# trezor.net
KiCad netlist of a schematic drawn in EAGLE
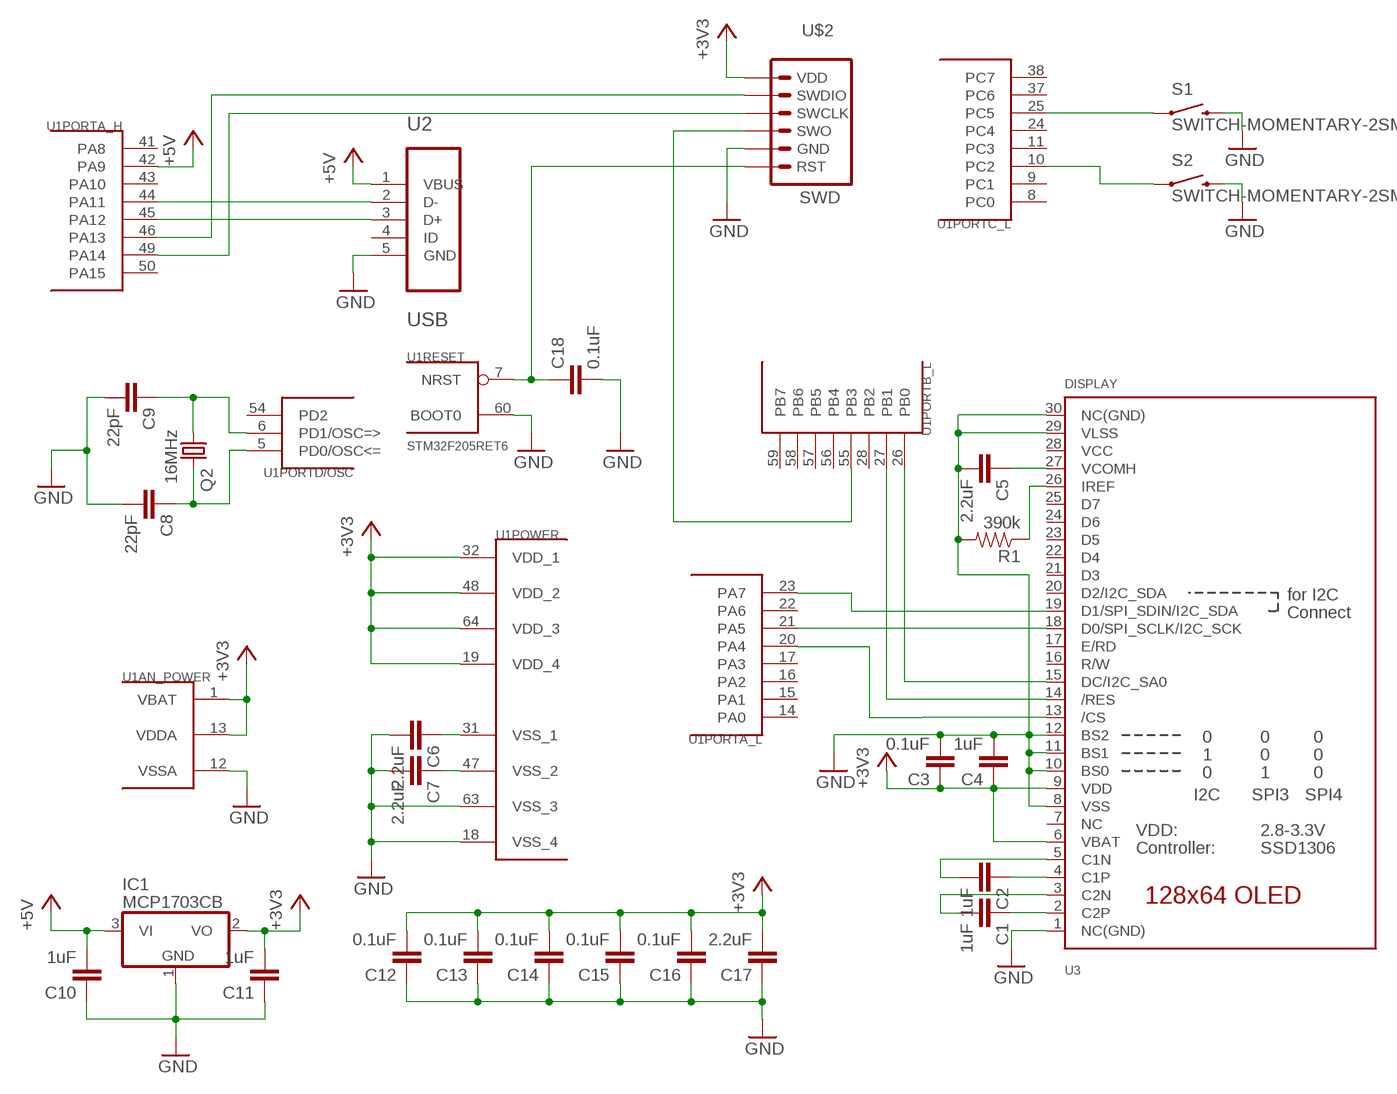
[diagram p0: schematic, sheet 1]

(export (version "E")
  (design (tool "Eeschema 10.0.6"))
  (components
    (comp (ref "C1")
      (value "1uF")
      (footprint "eagle-import:0603-CAP")
      (libsource (lib "eagle-import") (part "CAP0603-CAP"))
    )
    (comp (ref "C2")
      (value "1uF")
      (footprint "eagle-import:0603-CAP")
      (libsource (lib "eagle-import") (part "CAP0603-CAP"))
    )
    (comp (ref "C3")
      (value "0.1uF")
      (footprint "eagle-import:0603-CAP")
      (libsource (lib "eagle-import") (part "CAP0603-CAP"))
    )
    (comp (ref "C4")
      (value "1uF")
      (footprint "eagle-import:0603-CAP")
      (libsource (lib "eagle-import") (part "CAP0603-CAP"))
    )
    (comp (ref "C5")
      (value "2.2uF")
      (footprint "eagle-import:0603-CAP")
      (libsource (lib "eagle-import") (part "CAP0603-CAP"))
    )
    (comp (ref "C6")
      (value "2.2uF")
      (footprint "eagle-import:0603-CAP")
      (libsource (lib "eagle-import") (part "CAP0603-CAP"))
    )
    (comp (ref "C7")
      (value "2.2uF")
      (footprint "eagle-import:0603-CAP")
      (libsource (lib "eagle-import") (part "CAP0603-CAP"))
    )
    (comp (ref "C8")
      (value "22pF")
      (footprint "eagle-import:0603-CAP")
      (libsource (lib "eagle-import") (part "CAP0603-CAP"))
    )
    (comp (ref "C9")
      (value "22pF")
      (footprint "eagle-import:0603-CAP")
      (libsource (lib "eagle-import") (part "CAP0603-CAP"))
    )
    (comp (ref "C10")
      (value "1uF")
      (footprint "eagle-import:0603-CAP")
      (libsource (lib "eagle-import") (part "CAP0603-CAP"))
    )
    (comp (ref "C11")
      (value "1uF")
      (footprint "eagle-import:0603-CAP")
      (libsource (lib "eagle-import") (part "CAP0603-CAP"))
    )
    (comp (ref "C12")
      (value "0.1uF")
      (footprint "eagle-import:0603-CAP")
      (libsource (lib "eagle-import") (part "CAP0603-CAP"))
    )
    (comp (ref "C13")
      (value "0.1uF")
      (footprint "eagle-import:0603-CAP")
      (libsource (lib "eagle-import") (part "CAP0603-CAP"))
    )
    (comp (ref "C14")
      (value "0.1uF")
      (footprint "eagle-import:0603-CAP")
      (libsource (lib "eagle-import") (part "CAP0603-CAP"))
    )
    (comp (ref "C15")
      (value "0.1uF")
      (footprint "eagle-import:0603-CAP")
      (libsource (lib "eagle-import") (part "CAP0603-CAP"))
    )
    (comp (ref "C16")
      (value "0.1uF")
      (footprint "eagle-import:0603-CAP")
      (libsource (lib "eagle-import") (part "CAP0603-CAP"))
    )
    (comp (ref "C17")
      (value "2.2uF")
      (footprint "eagle-import:0603-CAP")
      (libsource (lib "eagle-import") (part "CAP0603-CAP"))
    )
    (comp (ref "C18")
      (value "0.1uF")
      (footprint "eagle-import:0603-CAP")
      (libsource (lib "eagle-import") (part "CAP0603-CAP"))
    )
    (comp (ref "IC1")
      (value "MCP1703CB")
      (footprint "eagle-import:SOT23")
      (libsource (lib "eagle-import") (part "MCP1703CB"))
    )
    (comp (ref "Q2")
      (value "16MHz")
      (footprint "eagle-import:CTS406")
      (libsource (lib "eagle-import") (part "CRYSTALCTS406"))
    )
    (comp (ref "R1")
      (value "390k")
      (footprint "eagle-import:0603-RES")
      (libsource (lib "eagle-import") (part "RESISTOR0603-RES"))
    )
    (comp (ref "S1")
      (value "SWITCH-MOMENTARY-2SMD")
      (footprint "eagle-import:TACTILE_SWITCH_SMD")
      (libsource (lib "eagle-import") (part "SWITCH-MOMENTARY-2SMD"))
    )
    (comp (ref "S2")
      (value "SWITCH-MOMENTARY-2SMD")
      (footprint "eagle-import:TACTILE_SWITCH_SMD")
      (libsource (lib "eagle-import") (part "SWITCH-MOMENTARY-2SMD"))
    )
    (comp (ref "U$2")
      (value "SWD")
      (footprint "eagle-import:SWD")
      (libsource (lib "eagle-import") (part "SWD"))
    )
    (comp (ref "U1")
      (value "STM32F205RET6")
      (footprint "eagle-import:TQFP64")
      (libsource (lib "eagle-import") (part "STM32F10XRXT6"))
    )
    (comp (ref "U2")
      (value "USB")
      (footprint "eagle-import:MOLEX_47346-0001")
      (fields (field (name "MPN") "47346-0001"))
      (libsource (lib "eagle-import") (part "47346-0001"))
    )
    (comp (ref "U3")
      (value "DISPLAY")
      (footprint "eagle-import:UG-2864HSWEG01_0.96IN_WRAPAROUND")
      (libsource (lib "eagle-import") (part "DISP_OLED_UG-2864HSWEG010.96{dblquote}"))
    )
  )
  (nets
    (net (code "1") (name "+3V3") (class "Default")
      (node (ref "C11") (pin "2") (pinfunction "2_2") (pintype "passive"))
      (node (ref "C12") (pin "2") (pinfunction "2_2") (pintype "passive"))
      (node (ref "C13") (pin "2") (pinfunction "2_2") (pintype "passive"))
      (node (ref "C14") (pin "2") (pinfunction "2_2") (pintype "passive"))
      (node (ref "C15") (pin "2") (pinfunction "2_2") (pintype "passive"))
      (node (ref "C16") (pin "2") (pinfunction "2_2") (pintype "passive"))
      (node (ref "C17") (pin "2") (pinfunction "2_2") (pintype "passive"))
      (node (ref "C3") (pin "1") (pinfunction "1_1") (pintype "passive"))
      (node (ref "C4") (pin "1") (pinfunction "1_1") (pintype "passive"))
      (node (ref "IC1") (pin "2") (pinfunction "VO_2") (pintype "passive"))
      (node (ref "U$2") (pin "6") (pinfunction "VDD_6") (pintype "passive"))
      (node (ref "U1") (pin "1") (pinfunction "VBAT_1") (pintype "power_in"))
      (node (ref "U1") (pin "13") (pinfunction "VDDA_13") (pintype "power_in"))
      (node (ref "U1") (pin "19") (pinfunction "VDD_4_19") (pintype "power_in"))
      (node (ref "U1") (pin "32") (pinfunction "VDD_1_32") (pintype "power_in"))
      (node (ref "U1") (pin "48") (pinfunction "VDD_2_48") (pintype "power_in"))
      (node (ref "U1") (pin "64") (pinfunction "VDD_3_64") (pintype "power_in"))
      (node (ref "U3") (pin "6") (pinfunction "VBAT_6") (pintype "input"))
      (node (ref "U3") (pin "9") (pinfunction "VDD_9") (pintype "power_in"))
    )
    (net (code "2") (name "+5V") (class "Default")
      (node (ref "C10") (pin "2") (pinfunction "2_2") (pintype "passive"))
      (node (ref "IC1") (pin "3") (pinfunction "VI_3") (pintype "input"))
      (node (ref "U1") (pin "42") (pinfunction "PA9_42") (pintype "bidirectional"))
      (node (ref "U2") (pin "1") (pinfunction "VBUS_1") (pintype "input"))
    )
    (net (code "3") (name "/VCC") (class "Default")
      (node (ref "U3") (pin "28") (pinfunction "VCC_28") (pintype "power_in"))
    )
    (net (code "4") (name "GND") (class "Default")
      (node (ref "C10") (pin "1") (pinfunction "1_1") (pintype "passive"))
      (node (ref "C11") (pin "1") (pinfunction "1_1") (pintype "passive"))
      (node (ref "C12") (pin "1") (pinfunction "1_1") (pintype "passive"))
      (node (ref "C13") (pin "1") (pinfunction "1_1") (pintype "passive"))
      (node (ref "C14") (pin "1") (pinfunction "1_1") (pintype "passive"))
      (node (ref "C15") (pin "1") (pinfunction "1_1") (pintype "passive"))
      (node (ref "C16") (pin "1") (pinfunction "1_1") (pintype "passive"))
      (node (ref "C17") (pin "1") (pinfunction "1_1") (pintype "passive"))
      (node (ref "C18") (pin "2") (pinfunction "2_2") (pintype "passive"))
      (node (ref "C3") (pin "2") (pinfunction "2_2") (pintype "passive"))
      (node (ref "C4") (pin "2") (pinfunction "2_2") (pintype "passive"))
      (node (ref "C5") (pin "2") (pinfunction "2_2") (pintype "passive"))
      (node (ref "C6") (pin "2") (pinfunction "2_2") (pintype "passive"))
      (node (ref "C7") (pin "2") (pinfunction "2_2") (pintype "passive"))
      (node (ref "C8") (pin "2") (pinfunction "2_2") (pintype "passive"))
      (node (ref "C9") (pin "2") (pinfunction "2_2") (pintype "passive"))
      (node (ref "IC1") (pin "1") (pinfunction "GND_1") (pintype "passive"))
      (node (ref "R1") (pin "2") (pinfunction "2_2") (pintype "passive"))
      (node (ref "S1") (pin "3") (pinfunction "2_3") (pintype "passive"))
      (node (ref "S2") (pin "3") (pinfunction "2_3") (pintype "passive"))
      (node (ref "U$2") (pin "2") (pinfunction "GND_2") (pintype "passive"))
      (node (ref "U1") (pin "12") (pinfunction "VSSA_12") (pintype "power_in"))
      (node (ref "U1") (pin "18") (pinfunction "VSS_4_18") (pintype "power_in"))
      (node (ref "U1") (pin "60") (pinfunction "BOOT0_60") (pintype "input"))
      (node (ref "U1") (pin "63") (pinfunction "VSS_3_63") (pintype "power_in"))
      (node (ref "U2") (pin "5") (pinfunction "GND_5") (pintype "input"))
      (node (ref "U3") (pin "1") (pinfunction "NC(GND)_1") (pintype "input"))
      (node (ref "U3") (pin "10") (pinfunction "BS0_10") (pintype "input"))
      (node (ref "U3") (pin "11") (pinfunction "BS1_11") (pintype "input"))
      (node (ref "U3") (pin "12") (pinfunction "BS2_12") (pintype "input"))
      (node (ref "U3") (pin "29") (pinfunction "VLSS_29") (pintype "power_in"))
      (node (ref "U3") (pin "30") (pinfunction "NC(GND)_30") (pintype "input"))
      (node (ref "U3") (pin "8") (pinfunction "VSS_8") (pintype "power_in"))
    )
    (net (code "5") (name "Net-(Q2-2)") (class "Default")
      (node (ref "C8") (pin "1") (pinfunction "1_1") (pintype "passive"))
      (node (ref "Q2") (pin "3") (pinfunction "2_3") (pintype "passive"))
      (node (ref "U1") (pin "5") (pinfunction "PD0/OSC<=_5") (pintype "bidirectional"))
    )
    (net (code "6") (name "Net-(U$2-RST)") (class "Default")
      (node (ref "C18") (pin "1") (pinfunction "1_1") (pintype "passive"))
      (node (ref "U$2") (pin "1") (pinfunction "RST_1") (pintype "passive"))
      (node (ref "U1") (pin "7") (pinfunction "NRST_7") (pintype "input"))
    )
    (net (code "7") (name "Net-(U$2-SWCLK)") (class "Default")
      (node (ref "U$2") (pin "4") (pinfunction "SWCLK_4") (pintype "passive"))
      (node (ref "U1") (pin "49") (pinfunction "PA14_49") (pintype "bidirectional"))
    )
    (net (code "8") (name "Net-(U$2-SWDIO)") (class "Default")
      (node (ref "U$2") (pin "5") (pinfunction "SWDIO_5") (pintype "passive"))
      (node (ref "U1") (pin "46") (pinfunction "PA13_46") (pintype "bidirectional"))
    )
    (net (code "9") (name "Net-(U$2-SWO)") (class "Default")
      (node (ref "U$2") (pin "3") (pinfunction "SWO_3") (pintype "passive"))
      (node (ref "U1") (pin "55") (pinfunction "PB3_55") (pintype "bidirectional"))
    )
    (net (code "10") (name "Net-(U1B-PA11)") (class "Default")
      (node (ref "U1") (pin "44") (pinfunction "PA11_44") (pintype "bidirectional"))
      (node (ref "U2") (pin "2") (pinfunction "D-_2") (pintype "input"))
    )
    (net (code "11") (name "Net-(U1B-PA12)") (class "Default")
      (node (ref "U1") (pin "45") (pinfunction "PA12_45") (pintype "bidirectional"))
      (node (ref "U2") (pin "3") (pinfunction "D+_3") (pintype "input"))
    )
    (net (code "12") (name "Net-(U1C-PA4)") (class "Default")
      (node (ref "U1") (pin "20") (pinfunction "PA4_20") (pintype "bidirectional"))
      (node (ref "U3") (pin "13") (pinfunction "/CS_13") (pintype "input"))
    )
    (net (code "13") (name "Net-(U1C-PA5)") (class "Default")
      (node (ref "U1") (pin "21") (pinfunction "PA5_21") (pintype "bidirectional"))
      (node (ref "U3") (pin "18") (pinfunction "D0/SPI_SCLK/I2C_SCK_18") (pintype "bidirectional"))
    )
    (net (code "14") (name "Net-(U1C-PA7)") (class "Default")
      (node (ref "U1") (pin "23") (pinfunction "PA7_23") (pintype "bidirectional"))
      (node (ref "U3") (pin "19") (pinfunction "D1/SPI_SDIN/I2C_SDA_19") (pintype "bidirectional"))
    )
    (net (code "15") (name "Net-(U1E-PB0)") (class "Default")
      (node (ref "U1") (pin "26") (pinfunction "PB0_26") (pintype "bidirectional"))
      (node (ref "U3") (pin "15") (pinfunction "DC/I2C_SA0_15") (pintype "input"))
    )
    (net (code "16") (name "Net-(U1E-PB1)") (class "Default")
      (node (ref "U1") (pin "27") (pinfunction "PB1_27") (pintype "bidirectional"))
      (node (ref "U3") (pin "14") (pinfunction "/RES_14") (pintype "input"))
    )
    (net (code "17") (name "Net-(U1G-PC2)") (class "Default")
      (node (ref "S2") (pin "1") (pinfunction "1_1") (pintype "passive"))
      (node (ref "U1") (pin "10") (pinfunction "PC2_10") (pintype "bidirectional"))
    )
    (net (code "18") (name "Net-(U1G-PC5)") (class "Default")
      (node (ref "S1") (pin "1") (pinfunction "1_1") (pintype "passive"))
      (node (ref "U1") (pin "25") (pinfunction "PC5_25") (pintype "bidirectional"))
    )
    (net (code "19") (name "Net-(U1H-PD1{slash}OSC=>)") (class "Default")
      (node (ref "C9") (pin "1") (pinfunction "1_1") (pintype "passive"))
      (node (ref "Q2") (pin "1") (pinfunction "1_1") (pintype "passive"))
      (node (ref "U1") (pin "6") (pinfunction "PD1/OSC=>_6") (pintype "bidirectional"))
    )
    (net (code "20") (name "Net-(U1I-VSS_1)") (class "Default")
      (node (ref "C6") (pin "1") (pinfunction "1_1") (pintype "passive"))
      (node (ref "U1") (pin "31") (pinfunction "VSS_1_31") (pintype "power_in"))
    )
    (net (code "21") (name "Net-(U1I-VSS_2)") (class "Default")
      (node (ref "C7") (pin "1") (pinfunction "1_1") (pintype "passive"))
      (node (ref "U1") (pin "47") (pinfunction "VSS_2_47") (pintype "power_in"))
    )
    (net (code "22") (name "Net-(U3-C1N)") (class "Default")
      (node (ref "C2") (pin "2") (pinfunction "2_2") (pintype "passive"))
      (node (ref "U3") (pin "5") (pinfunction "C1N_5") (pintype "input"))
    )
    (net (code "23") (name "Net-(U3-C1P)") (class "Default")
      (node (ref "C2") (pin "1") (pinfunction "1_1") (pintype "passive"))
      (node (ref "U3") (pin "4") (pinfunction "C1P_4") (pintype "input"))
    )
    (net (code "24") (name "Net-(U3-C2N)") (class "Default")
      (node (ref "C1") (pin "2") (pinfunction "2_2") (pintype "passive"))
      (node (ref "U3") (pin "3") (pinfunction "C2N_3") (pintype "input"))
    )
    (net (code "25") (name "Net-(U3-C2P)") (class "Default")
      (node (ref "C1") (pin "1") (pinfunction "1_1") (pintype "passive"))
      (node (ref "U3") (pin "2") (pinfunction "C2P_2") (pintype "input"))
    )
    (net (code "26") (name "Net-(U3-IREF)") (class "Default")
      (node (ref "R1") (pin "1") (pinfunction "1_1") (pintype "passive"))
      (node (ref "U3") (pin "26") (pinfunction "IREF_26") (pintype "input"))
    )
    (net (code "27") (name "Net-(U3-VCOMH)") (class "Default")
      (node (ref "C5") (pin "1") (pinfunction "1_1") (pintype "passive"))
      (node (ref "U3") (pin "27") (pinfunction "VCOMH_27") (pintype "output"))
    )
    (net (code "28") (name "unconnected-(U1B-PA8-Pad41)") (class "Default")
      (node (ref "U1") (pin "41") (pinfunction "PA8_41") (pintype "bidirectional"))
    )
    (net (code "29") (name "unconnected-(U1B-PA10-Pad43)") (class "Default")
      (node (ref "U1") (pin "43") (pinfunction "PA10_43") (pintype "bidirectional"))
    )
    (net (code "30") (name "unconnected-(U1B-PA15-Pad50)") (class "Default")
      (node (ref "U1") (pin "50") (pinfunction "PA15_50") (pintype "bidirectional"))
    )
    (net (code "31") (name "unconnected-(U1C-PA0-Pad14)") (class "Default")
      (node (ref "U1") (pin "14") (pinfunction "PA0_14") (pintype "bidirectional"))
    )
    (net (code "32") (name "unconnected-(U1C-PA1-Pad15)") (class "Default")
      (node (ref "U1") (pin "15") (pinfunction "PA1_15") (pintype "bidirectional"))
    )
    (net (code "33") (name "unconnected-(U1C-PA2-Pad16)") (class "Default")
      (node (ref "U1") (pin "16") (pinfunction "PA2_16") (pintype "bidirectional"))
    )
    (net (code "34") (name "unconnected-(U1C-PA3-Pad17)") (class "Default")
      (node (ref "U1") (pin "17") (pinfunction "PA3_17") (pintype "bidirectional"))
    )
    (net (code "35") (name "unconnected-(U1C-PA6-Pad22)") (class "Default")
      (node (ref "U1") (pin "22") (pinfunction "PA6_22") (pintype "bidirectional"))
    )
    (net (code "36") (name "unconnected-(U1E-PB2-Pad28)") (class "Default")
      (node (ref "U1") (pin "28") (pinfunction "PB2_28") (pintype "bidirectional"))
    )
    (net (code "37") (name "unconnected-(U1E-PB4-Pad56)") (class "Default")
      (node (ref "U1") (pin "56") (pinfunction "PB4_56") (pintype "bidirectional"))
    )
    (net (code "38") (name "unconnected-(U1E-PB5-Pad57)") (class "Default")
      (node (ref "U1") (pin "57") (pinfunction "PB5_57") (pintype "bidirectional"))
    )
    (net (code "39") (name "unconnected-(U1E-PB6-Pad58)") (class "Default")
      (node (ref "U1") (pin "58") (pinfunction "PB6_58") (pintype "bidirectional"))
    )
    (net (code "40") (name "unconnected-(U1E-PB7-Pad59)") (class "Default")
      (node (ref "U1") (pin "59") (pinfunction "PB7_59") (pintype "bidirectional"))
    )
    (net (code "41") (name "unconnected-(U1G-PC0-Pad8)") (class "Default")
      (node (ref "U1") (pin "8") (pinfunction "PC0_8") (pintype "bidirectional"))
    )
    (net (code "42") (name "unconnected-(U1G-PC1-Pad9)") (class "Default")
      (node (ref "U1") (pin "9") (pinfunction "PC1_9") (pintype "bidirectional"))
    )
    (net (code "43") (name "unconnected-(U1G-PC3-Pad11)") (class "Default")
      (node (ref "U1") (pin "11") (pinfunction "PC3_11") (pintype "bidirectional"))
    )
    (net (code "44") (name "unconnected-(U1G-PC4-Pad24)") (class "Default")
      (node (ref "U1") (pin "24") (pinfunction "PC4_24") (pintype "bidirectional"))
    )
    (net (code "45") (name "unconnected-(U1G-PC6-Pad37)") (class "Default")
      (node (ref "U1") (pin "37") (pinfunction "PC6_37") (pintype "bidirectional"))
    )
    (net (code "46") (name "unconnected-(U1G-PC7-Pad38)") (class "Default")
      (node (ref "U1") (pin "38") (pinfunction "PC7_38") (pintype "bidirectional"))
    )
    (net (code "47") (name "unconnected-(U1H-PD2-Pad54)") (class "Default")
      (node (ref "U1") (pin "54") (pinfunction "PD2_54") (pintype "bidirectional"))
    )
    (net (code "48") (name "unconnected-(U2-ID-Pad4)") (class "Default")
      (node (ref "U2") (pin "4") (pinfunction "ID_4") (pintype "input"))
    )
    (net (code "49") (name "unconnected-(U3-D2{slash}I2C_SDA-Pad20)") (class "Default")
      (node (ref "U3") (pin "20") (pinfunction "D2/I2C_SDA_20") (pintype "bidirectional"))
    )
    (net (code "50") (name "unconnected-(U3-D3-Pad21)") (class "Default")
      (node (ref "U3") (pin "21") (pinfunction "D3_21") (pintype "bidirectional"))
    )
    (net (code "51") (name "unconnected-(U3-D4-Pad22)") (class "Default")
      (node (ref "U3") (pin "22") (pinfunction "D4_22") (pintype "bidirectional"))
    )
    (net (code "52") (name "unconnected-(U3-D5-Pad23)") (class "Default")
      (node (ref "U3") (pin "23") (pinfunction "D5_23") (pintype "bidirectional"))
    )
    (net (code "53") (name "unconnected-(U3-D6-Pad24)") (class "Default")
      (node (ref "U3") (pin "24") (pinfunction "D6_24") (pintype "bidirectional"))
    )
    (net (code "54") (name "unconnected-(U3-D7-Pad25)") (class "Default")
      (node (ref "U3") (pin "25") (pinfunction "D7_25") (pintype "bidirectional"))
    )
    (net (code "55") (name "unconnected-(U3-E{slash}RD-Pad17)") (class "Default")
      (node (ref "U3") (pin "17") (pinfunction "E/RD_17") (pintype "input"))
    )
    (net (code "56") (name "unconnected-(U3-NC-Pad7)") (class "Default")
      (node (ref "U3") (pin "7") (pinfunction "NC_7") (pintype "no_connect"))
    )
    (net (code "57") (name "unconnected-(U3-R{slash}W-Pad16)") (class "Default")
      (node (ref "U3") (pin "16") (pinfunction "R/W_16") (pintype "input"))
    )
  )
)
